# bidirectional_switch_N.net
KiCad netlist of a schematic drawn in Altium Designer
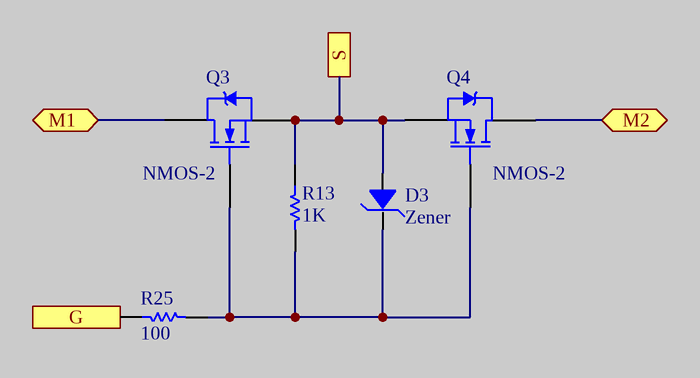
[diagram p0: bidirectional_switch_N.SchDoc]

(export (version "E")
  (design (tool "Eeschema 10.0.6"))
  (components
    (comp (ref "D3") (value "Zener") (footprint "ZENER") (libsource (lib "eLIB") (part "Zener")))
    (comp (ref "Q3")
      (value "NMOS-2")
      (footprint "dpak")
      (description "N-Channel Power MOSFET")
      (fields (field (name "PUBLISHER") "Altium Limited"))
      (libsource (lib "eLIB") (part "NMOS-2"))
    )
    (comp (ref "Q4")
      (value "NMOS-2")
      (footprint "dpak")
      (description "N-Channel Power MOSFET")
      (fields (field (name "PUBLISHER") "Altium Limited"))
      (libsource (lib "eLIB") (part "NMOS-2"))
    )
    (comp (ref "R13")
      (value "1K")
      (footprint "RESC0603")
      (description "0603,0.1W")
      (fields (field (name "PUBLISHER") "Altium Limited"))
      (libsource (lib "eLIB") (part "Resistor"))
    )
    (comp (ref "R25")
      (value "100")
      (footprint "RESC0603")
      (description "0603,0.1W")
      (fields (field (name "PUBLISHER") "Altium Limited"))
      (libsource (lib "eLIB") (part "Resistor"))
    )
  )
  (nets
    (net (code "1") (name "/G") (class "Default")
      (node (ref "R25") (pin "1") (pinfunction "1_1") (pintype "passive"))
    )
    (net (code "2") (name "/M1") (class "Default")
      (node (ref "Q3") (pin "2") (pinfunction "D_2") (pintype "passive"))
    )
    (net (code "3") (name "/M2") (class "Default")
      (node (ref "Q4") (pin "2") (pinfunction "D_2") (pintype "passive"))
    )
    (net (code "4") (name "/S") (class "Default")
      (node (ref "D3") (pin "1") (pinfunction "A_1") (pintype "passive"))
      (node (ref "Q3") (pin "3") (pinfunction "S_3") (pintype "passive"))
      (node (ref "Q4") (pin "3") (pinfunction "S_3") (pintype "passive"))
      (node (ref "R13") (pin "1") (pinfunction "1_1") (pintype "passive"))
    )
    (net (code "5") (name "Net-(D3-K)") (class "Default")
      (node (ref "D3") (pin "2") (pinfunction "K_2") (pintype "passive"))
      (node (ref "Q3") (pin "1") (pinfunction "G_1") (pintype "passive"))
      (node (ref "Q4") (pin "1") (pinfunction "G_1") (pintype "passive"))
      (node (ref "R13") (pin "2") (pinfunction "2_2") (pintype "passive"))
      (node (ref "R25") (pin "2") (pinfunction "2_2") (pintype "passive"))
    )
  )
)
